# cell_phone_detector.net
KiCad netlist of a schematic drawn in EAGLE
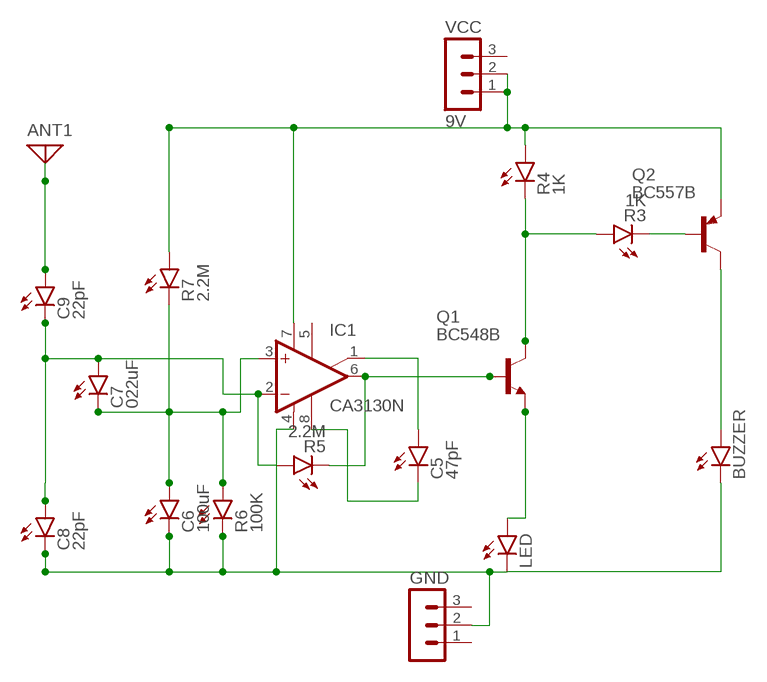
[diagram p0: schematic, sheet 1]

(export (version "E")
  (design (tool "Eeschema 10.0.6"))
  (components
    (comp (ref "ANT1")
      (value "ANTENNA")
      (footprint "eagle-import:PAD-01")
      (libsource (lib "eagle-import") (part "ANTENNA"))
    )
    (comp (ref "BUZZER")
      (value "LED5MM")
      (footprint "eagle-import:LED5MM")
      (libsource (lib "eagle-import") (part "LED5MM"))
    )
    (comp (ref "C5")
      (value "47pF")
      (footprint "eagle-import:LED5MM")
      (libsource (lib "eagle-import") (part "LED5MM"))
    )
    (comp (ref "C6")
      (value "100uF")
      (footprint "eagle-import:LED5MM")
      (libsource (lib "eagle-import") (part "LED5MM"))
    )
    (comp (ref "C7")
      (value "022uF")
      (footprint "eagle-import:LED5MM")
      (libsource (lib "eagle-import") (part "LED5MM"))
    )
    (comp (ref "C8")
      (value "22pF")
      (footprint "eagle-import:LED5MM")
      (libsource (lib "eagle-import") (part "LED5MM"))
    )
    (comp (ref "C9")
      (value "22pF")
      (footprint "eagle-import:LED5MM")
      (libsource (lib "eagle-import") (part "LED5MM"))
    )
    (comp (ref "GND")
      (value "MA03-1")
      (footprint "eagle-import:MA03-1")
      (libsource (lib "eagle-import") (part "MA03-1"))
    )
    (comp (ref "IC1")
      (value "CA3130N")
      (footprint "eagle-import:DIL08")
      (libsource (lib "eagle-import") (part "CA3130N"))
    )
    (comp (ref "LED")
      (value "LED5MM")
      (footprint "eagle-import:LED5MM")
      (libsource (lib "eagle-import") (part "LED5MM"))
    )
    (comp (ref "Q1")
      (value "BC548B")
      (footprint "eagle-import:TO92-EBC")
      (libsource (lib "eagle-import") (part "BC548B"))
    )
    (comp (ref "Q2")
      (value "BC557B")
      (footprint "eagle-import:TO92-EBC")
      (libsource (lib "eagle-import") (part "BC557B"))
    )
    (comp (ref "R3")
      (value "1K")
      (footprint "eagle-import:LED5MM")
      (libsource (lib "eagle-import") (part "LED5MM"))
    )
    (comp (ref "R4")
      (value "1K")
      (footprint "eagle-import:LED5MM")
      (libsource (lib "eagle-import") (part "LED5MM"))
    )
    (comp (ref "R5")
      (value "2.2M")
      (footprint "eagle-import:LED5MM")
      (libsource (lib "eagle-import") (part "LED5MM"))
    )
    (comp (ref "R6")
      (value "100K")
      (footprint "eagle-import:LED5MM")
      (libsource (lib "eagle-import") (part "LED5MM"))
    )
    (comp (ref "R7")
      (value "2.2M")
      (footprint "eagle-import:LED5MM")
      (libsource (lib "eagle-import") (part "LED5MM"))
    )
    (comp (ref "VCC")
      (value "9V")
      (footprint "eagle-import:MA03-1")
      (libsource (lib "eagle-import") (part "MA03-1"))
    )
  )
  (nets
    (net (code "1") (name "Net-(ANT1-Pad1)") (class "Default")
      (node (ref "ANT1") (pin "1") (pinfunction "1_1") (pintype "output"))
      (node (ref "C9") (pin "A") (pinfunction "A_A") (pintype "passive"))
    )
    (net (code "2") (name "Net-(BUZZER-C)") (class "Default")
      (node (ref "BUZZER") (pin "K") (pinfunction "C_K") (pintype "passive"))
      (node (ref "C6") (pin "K") (pinfunction "C_K") (pintype "passive"))
      (node (ref "C8") (pin "K") (pinfunction "C_K") (pintype "passive"))
      (node (ref "GND") (pin "2") (pinfunction "2_2") (pintype "passive"))
      (node (ref "IC1") (pin "4") (pinfunction "V-_4") (pintype "power_in"))
      (node (ref "LED") (pin "K") (pinfunction "C_K") (pintype "passive"))
      (node (ref "R6") (pin "K") (pinfunction "C_K") (pintype "passive"))
    )
    (net (code "3") (name "Net-(BUZZER-PadA)") (class "Default")
      (node (ref "BUZZER") (pin "A") (pinfunction "A_A") (pintype "passive"))
      (node (ref "Q2") (pin "C") (pinfunction "C_C") (pintype "passive"))
    )
    (net (code "4") (name "Net-(C5-C)") (class "Default")
      (node (ref "C5") (pin "K") (pinfunction "C_K") (pintype "passive"))
      (node (ref "IC1") (pin "8") (pinfunction "CMP_8") (pintype "passive"))
    )
    (net (code "5") (name "Net-(C7-C)") (class "Default")
      (node (ref "C6") (pin "A") (pinfunction "A_A") (pintype "passive"))
      (node (ref "C7") (pin "K") (pinfunction "C_K") (pintype "passive"))
      (node (ref "IC1") (pin "3") (pinfunction "+IN_3") (pintype "input"))
      (node (ref "R6") (pin "A") (pinfunction "A_A") (pintype "passive"))
      (node (ref "R7") (pin "K") (pinfunction "C_K") (pintype "passive"))
    )
    (net (code "6") (name "Net-(C9-C)") (class "Default")
      (node (ref "C7") (pin "A") (pinfunction "A_A") (pintype "passive"))
      (node (ref "C8") (pin "A") (pinfunction "A_A") (pintype "passive"))
      (node (ref "C9") (pin "K") (pinfunction "C_K") (pintype "passive"))
      (node (ref "IC1") (pin "2") (pinfunction "-IN_2") (pintype "input"))
      (node (ref "R5") (pin "A") (pinfunction "A_A") (pintype "passive"))
    )
    (net (code "7") (name "Net-(IC1-ON{slash}CMP)") (class "Default")
      (node (ref "C5") (pin "A") (pinfunction "A_A") (pintype "passive"))
      (node (ref "IC1") (pin "1") (pinfunction "ON/CMP_1") (pintype "passive"))
    )
    (net (code "8") (name "Net-(IC1-OUT)") (class "Default")
      (node (ref "IC1") (pin "6") (pinfunction "OUT_6") (pintype "output"))
      (node (ref "Q1") (pin "B") (pinfunction "B_B") (pintype "passive"))
      (node (ref "R5") (pin "K") (pinfunction "C_K") (pintype "passive"))
    )
    (net (code "9") (name "Net-(IC1-V+)") (class "Default")
      (node (ref "IC1") (pin "7") (pinfunction "V+_7") (pintype "power_in"))
      (node (ref "Q2") (pin "E") (pinfunction "E_E") (pintype "passive"))
      (node (ref "R4") (pin "A") (pinfunction "A_A") (pintype "passive"))
      (node (ref "R7") (pin "A") (pinfunction "A_A") (pintype "passive"))
      (node (ref "VCC") (pin "1") (pinfunction "1_1") (pintype "passive"))
      (node (ref "VCC") (pin "2") (pinfunction "2_2") (pintype "passive"))
    )
    (net (code "10") (name "Net-(LED-PadA)") (class "Default")
      (node (ref "LED") (pin "A") (pinfunction "A_A") (pintype "passive"))
      (node (ref "Q1") (pin "E") (pinfunction "E_E") (pintype "passive"))
    )
    (net (code "11") (name "Net-(R3-C)") (class "Default")
      (node (ref "Q2") (pin "B") (pinfunction "B_B") (pintype "passive"))
      (node (ref "R3") (pin "K") (pinfunction "C_K") (pintype "passive"))
    )
    (net (code "12") (name "Net-(R4-C)") (class "Default")
      (node (ref "Q1") (pin "C") (pinfunction "C_C") (pintype "passive"))
      (node (ref "R3") (pin "A") (pinfunction "A_A") (pintype "passive"))
      (node (ref "R4") (pin "K") (pinfunction "C_K") (pintype "passive"))
    )
    (net (code "13") (name "unconnected-(GND-Pad1)") (class "Default")
      (node (ref "GND") (pin "1") (pinfunction "1_1") (pintype "passive"))
    )
    (net (code "14") (name "unconnected-(GND-Pad3)") (class "Default")
      (node (ref "GND") (pin "3") (pinfunction "3_3") (pintype "passive"))
    )
    (net (code "15") (name "unconnected-(IC1-ON-Pad5)") (class "Default")
      (node (ref "IC1") (pin "5") (pinfunction "ON_5") (pintype "passive"))
    )
    (net (code "16") (name "unconnected-(VCC-Pad3)") (class "Default")
      (node (ref "VCC") (pin "3") (pinfunction "3_3") (pintype "passive"))
    )
  )
)
